# 4_half.net
KiCad netlist of a schematic drawn in Altium Designer
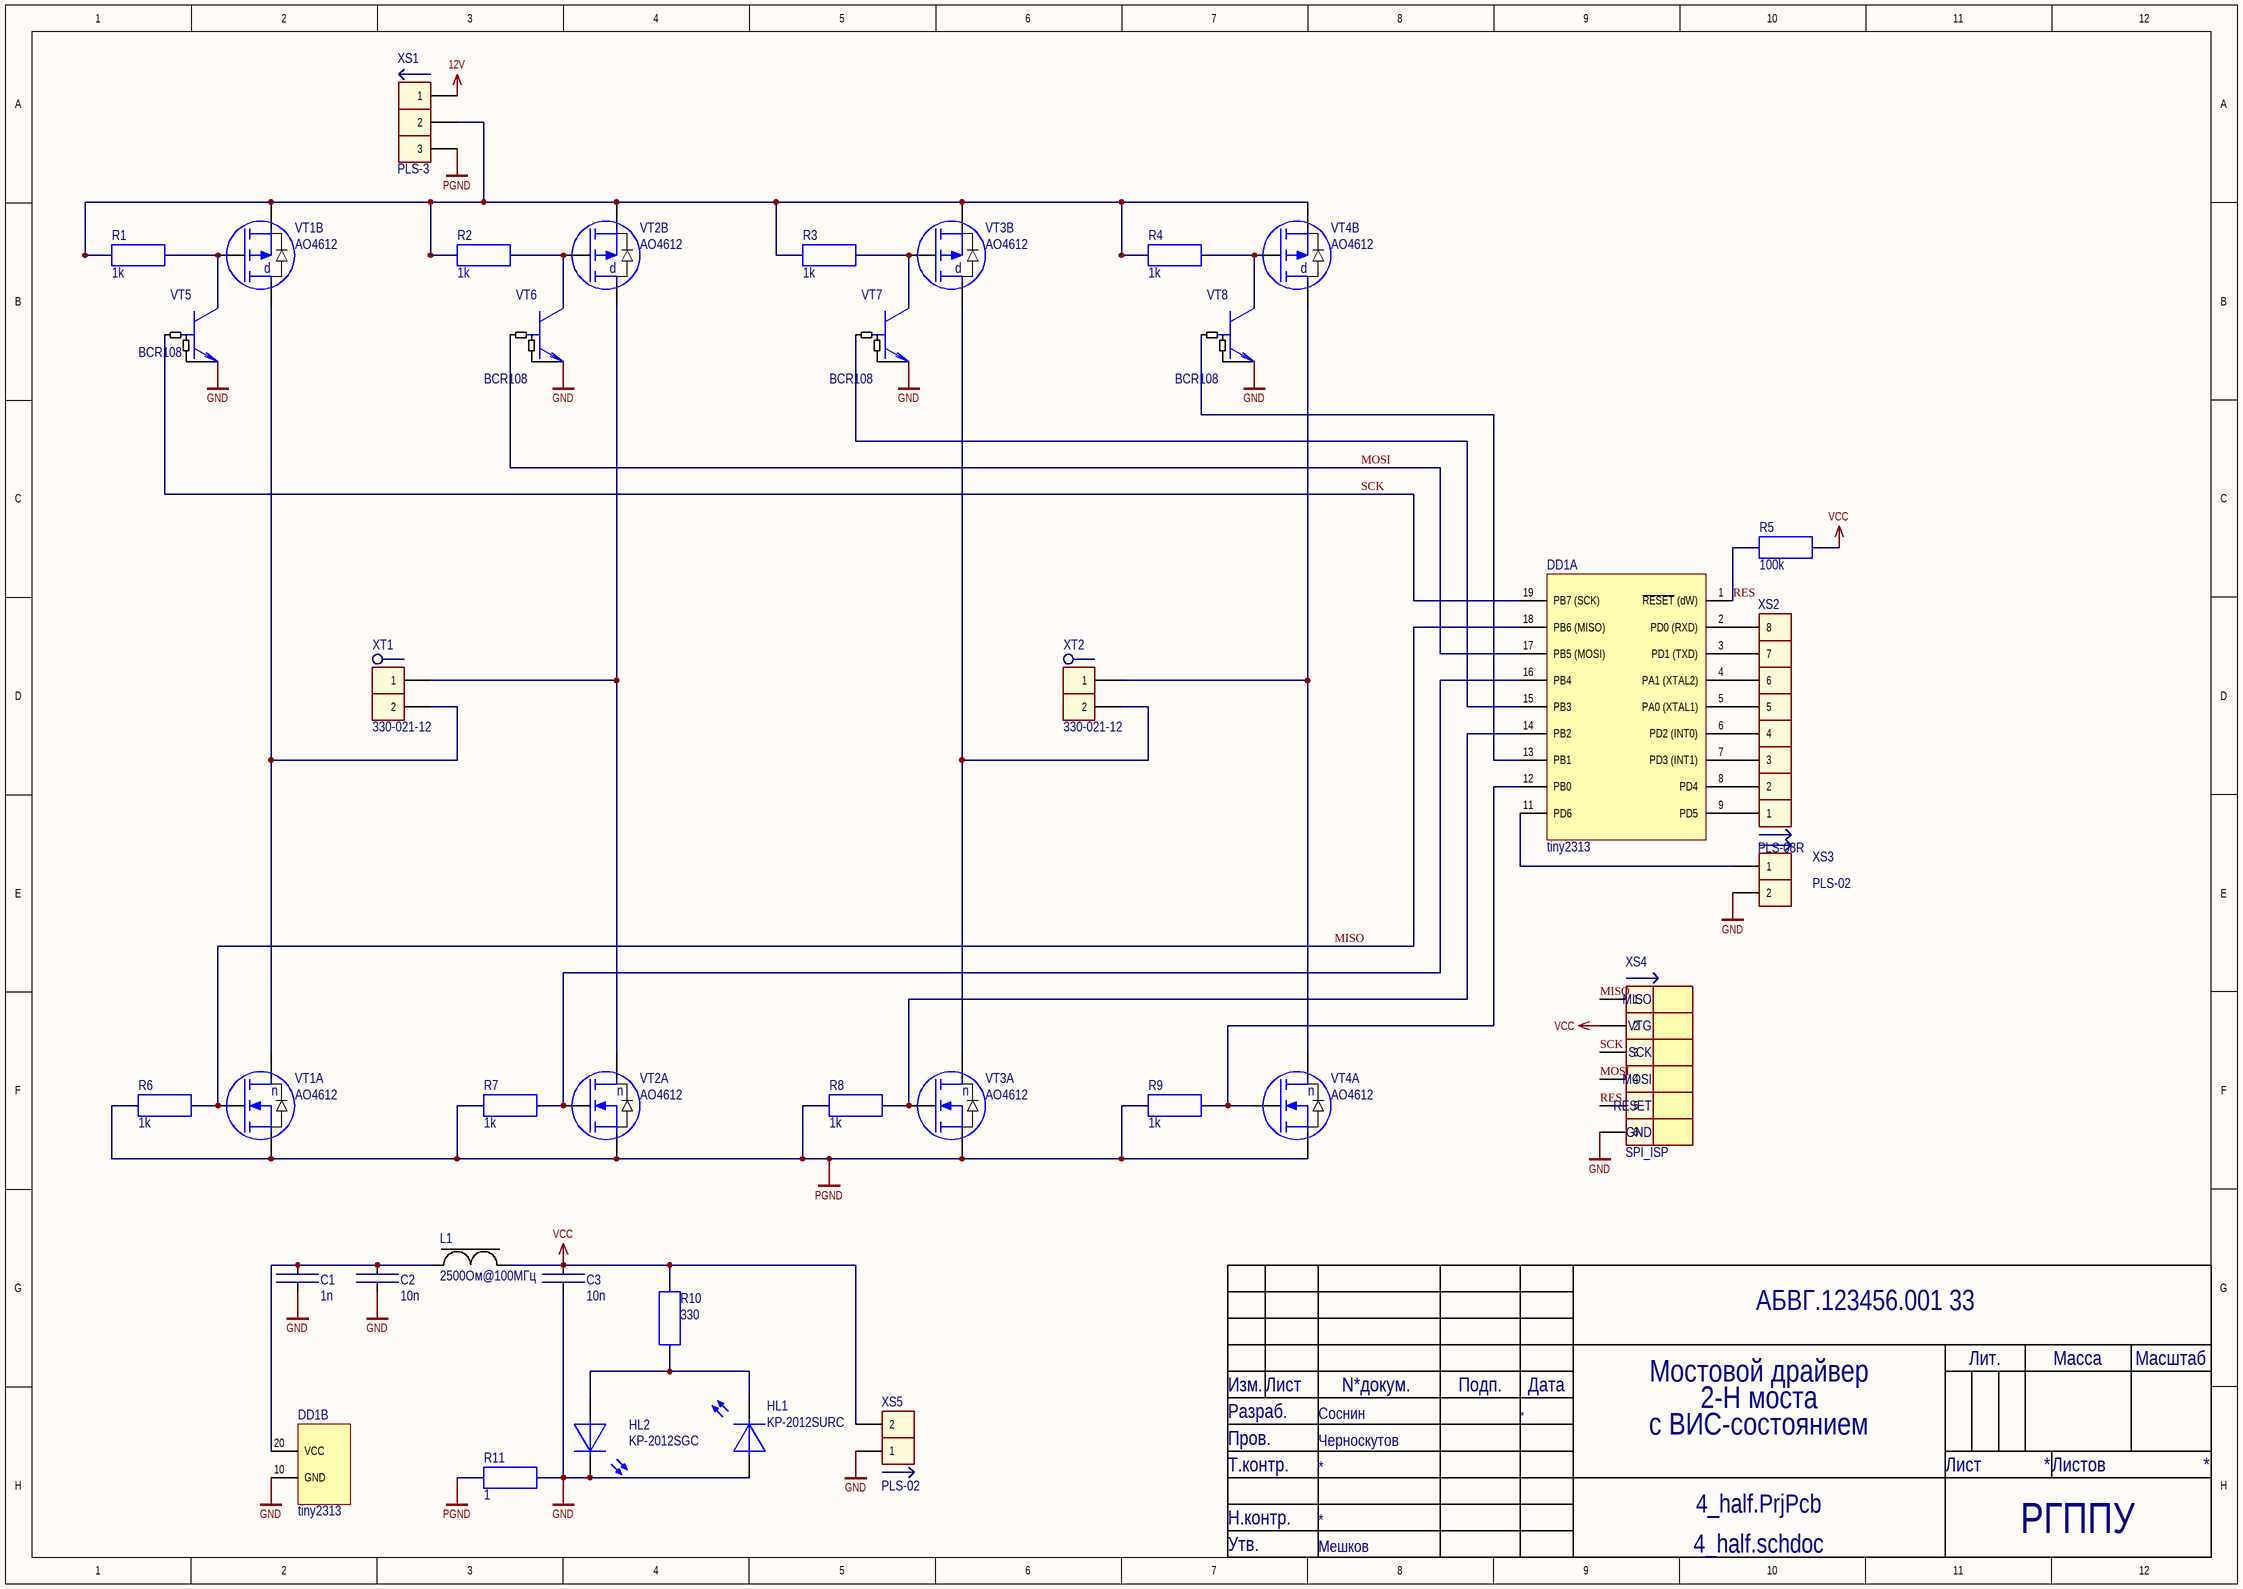
[diagram p0: 4_half.schdoc]

(export (version "E")
  (design (tool "Eeschema 10.0.6"))
  (components
    (comp (ref "C1")
      (value "1n")
      (footprint "SMDRC0805")
      (description "Generic capasitor non-polar")
      (fields (field (name "PARTNUMBER") "Capacitor 0805 1n"))
      (libsource (lib "library") (part "Capacitor"))
    )
    (comp (ref "C2")
      (value "10n")
      (footprint "SMDRC0805")
      (description "Generic capasitor non-polar")
      (fields (field (name "PARTNUMBER") "Capacitor 0805 10n"))
      (libsource (lib "library") (part "Capacitor"))
    )
    (comp (ref "C3")
      (value "10n")
      (footprint "SMDRC0805")
      (description "Generic capasitor non-polar")
      (fields (field (name "PARTNUMBER") "Capacitor 0805 10n"))
      (libsource (lib "library") (part "Capacitor"))
    )
    (comp (ref "DD1")
      (value "tiny2313")
      (footprint "Standard:DIP20")
      (description "Microcontroller 8-bit")
      (fields (field (name "MANUFACTURERPARTNUMBER") "ATTINY2313A-PU") (field (name "MANUFACTURER") "Atmel"))
      (libsource (lib "") (part "ATTINY2313A-PU_1"))
    )
    (comp (ref "HL1")
      (value "KP-2012SURC")
      (footprint "Indicator:DIOMELF2012M")
      (description "Diod LED SMD Red")
      (libsource (lib "Indicator") (part "LED1_R"))
    )
    (comp (ref "HL2")
      (value "KP-2012SGC")
      (footprint "Indicator:DIOMELF2012M")
      (description "Diod LED SMD Green")
      (libsource (lib "Indicator") (part "LED1_G"))
    )
    (comp (ref "L1")
      (value "2500Ом@100МГц")
      (footprint "Inductor:MMZ1608")
      (description "Феррит 2500Ом@100МГц")
      (fields (field (name "MANUFACTURERPARTNUMBER") "MMZ1608A252B") (field (name "MANUFACTURER") "TDK"))
      (libsource (lib "Inductor") (part "MMZ1608A252B"))
    )
    (comp (ref "R1")
      (value "1k")
      (footprint "SMDRC0805")
      (description "Generic resistor")
      (fields (field (name "PARTNUMBER") "Resistor 0805 1k"))
      (libsource (lib "library") (part "Resistor"))
    )
    (comp (ref "R2")
      (value "1k")
      (footprint "SMDRC0805")
      (description "Generic resistor")
      (fields (field (name "PARTNUMBER") "Resistor 0805 1k"))
      (libsource (lib "library") (part "Resistor"))
    )
    (comp (ref "R3")
      (value "1k")
      (footprint "SMDRC0805")
      (description "Generic resistor")
      (fields (field (name "PARTNUMBER") "Resistor 0805 1k"))
      (libsource (lib "library") (part "Resistor"))
    )
    (comp (ref "R4")
      (value "1k")
      (footprint "SMDRC0805")
      (description "Generic resistor")
      (fields (field (name "PARTNUMBER") "Resistor 0805 1k"))
      (libsource (lib "library") (part "Resistor"))
    )
    (comp (ref "R5")
      (value "100k")
      (footprint "SMDRC0805")
      (description "Generic resistor")
      (fields (field (name "PARTNUMBER") "Resistor 0805 100k"))
      (libsource (lib "library") (part "Resistor"))
    )
    (comp (ref "R6")
      (value "1k")
      (footprint "SMDRC0805")
      (description "Generic resistor")
      (fields (field (name "PARTNUMBER") "Resistor 0805 1k"))
      (libsource (lib "library") (part "Resistor"))
    )
    (comp (ref "R7")
      (value "1k")
      (footprint "SMDRC0805")
      (description "Generic resistor")
      (fields (field (name "PARTNUMBER") "Resistor 0805 1k"))
      (libsource (lib "library") (part "Resistor"))
    )
    (comp (ref "R8")
      (value "1k")
      (footprint "SMDRC0805")
      (description "Generic resistor")
      (fields (field (name "PARTNUMBER") "Resistor 0805 1k"))
      (libsource (lib "library") (part "Resistor"))
    )
    (comp (ref "R9")
      (value "1k")
      (footprint "SMDRC0805")
      (description "Generic resistor")
      (fields (field (name "PARTNUMBER") "Resistor 0805 1k"))
      (libsource (lib "library") (part "Resistor"))
    )
    (comp (ref "R10")
      (value "330")
      (footprint "SMDRC0805")
      (description "Generic resistor")
      (fields (field (name "PARTNUMBER") "Resistor 0805 330"))
      (libsource (lib "") (part "Resistor_1"))
    )
    (comp (ref "R11")
      (value "1")
      (footprint "SMDRC0805")
      (description "Generic resistor")
      (fields (field (name "PARTNUMBER") "Resistor 0805 1"))
      (libsource (lib "library") (part "Resistor"))
    )
    (comp (ref "VT1")
      (value "AO4612")
      (footprint "Standard:SOIC-8-Narrow")
      (description "p-n пара комплиментарная 60В")
      (fields (field (name "MANUFACTURER") "AO (Alpha & Omega semiconductor)"))
      (libsource (lib "Transistor") (part "AO4612"))
    )
    (comp (ref "VT2")
      (value "AO4612")
      (footprint "Standard:SOIC-8-Narrow")
      (description "p-n пара комплиментарная 60В")
      (fields (field (name "MANUFACTURER") "AO (Alpha & Omega semiconductor)"))
      (libsource (lib "Transistor") (part "AO4612"))
    )
    (comp (ref "VT3")
      (value "AO4612")
      (footprint "Standard:SOIC-8-Narrow")
      (description "p-n пара комплиментарная 60В")
      (fields (field (name "MANUFACTURER") "AO (Alpha & Omega semiconductor)"))
      (libsource (lib "Transistor") (part "AO4612"))
    )
    (comp (ref "VT4")
      (value "AO4612")
      (footprint "Standard:SOIC-8-Narrow")
      (description "p-n пара комплиментарная 60В")
      (fields (field (name "MANUFACTURER") "AO (Alpha & Omega semiconductor)"))
      (libsource (lib "Transistor") (part "AO4612"))
    )
    (comp (ref "VT5")
      (value "BCR108")
      (footprint "Transistor:SOT95P245X110-3M")
      (description "n-p-n цифровой")
      (fields
        (field (name "MANUFACTURER") "Infineon Technologies")
        (field (name "MANUFACTURERPARTNUMBER") "BCR108E6327")
      )
      (libsource (lib "Transistor") (part "BCR108E6327"))
    )
    (comp (ref "VT6")
      (value "BCR108")
      (footprint "Transistor:SOT95P245X110-3M")
      (description "n-p-n цифровой")
      (fields
        (field (name "MANUFACTURER") "Infineon Technologies")
        (field (name "MANUFACTURERPARTNUMBER") "BCR108E6327")
      )
      (libsource (lib "Transistor") (part "BCR108E6327"))
    )
    (comp (ref "VT7")
      (value "BCR108")
      (footprint "Transistor:SOT95P245X110-3M")
      (description "n-p-n цифровой")
      (fields
        (field (name "MANUFACTURER") "Infineon Technologies")
        (field (name "MANUFACTURERPARTNUMBER") "BCR108E6327")
      )
      (libsource (lib "Transistor") (part "BCR108E6327"))
    )
    (comp (ref "VT8")
      (value "BCR108")
      (footprint "Transistor:SOT95P245X110-3M")
      (description "n-p-n цифровой")
      (fields
        (field (name "MANUFACTURER") "Infineon Technologies")
        (field (name "MANUFACTURERPARTNUMBER") "BCR108E6327")
      )
      (libsource (lib "Transistor") (part "BCR108E6327"))
    )
    (comp (ref "XS1")
      (value "partnumber")
      (footprint "Connector:PLS-03")
      (description "Male 3-pin connection")
      (fields (field (name "MANUFACTURERPARTNUMBER") "PLS-3"))
      (libsource (lib "Connector") (part "Con3_M_PLS-3"))
    )
    (comp (ref "XS2")
      (value "partnumber")
      (footprint "Connector:PLS-08R1")
      (description "Male 8-pin connection")
      (fields (field (name "MANUFACTURERPARTNUMBER") "PLS-08R"))
      (libsource (lib "Connector") (part "Con8_M PLS-08MR"))
    )
    (comp (ref "XS3")
      (value "PLS-02")
      (footprint "Connector:PLS-02")
      (description "Male 2-pin connection")
      (fields (field (name "MANUFACTURER") "AUK"))
      (libsource (lib "") (part "Con2_M_PLS-02_1"))
    )
    (comp (ref "XS4")
      (value "SPI_ISP")
      (footprint "Connector:IDC-06M")
      (description "SPI connector")
      (fields (field (name "MANUFACTURERPARTNUMBER") "IDC-06M"))
      (libsource (lib "Connector") (part "Con6_M IDC-06M_SPI"))
    )
    (comp (ref "XS5")
      (value "PLS-02")
      (footprint "Connector:PLS-02")
      (description "Male 2-pin connection")
      (fields (field (name "MANUFACTURER") "AUK"))
      (libsource (lib "Connector") (part "Con2_M_PLS-02"))
    )
    (comp (ref "XT1")
      (value "330-021-12")
      (footprint "330-021-12")
      (description "Demountable connection  2-pin")
      (fields (field (name "MANUFACTURER") "Degson Electronics Co., Ltd"))
      (libsource (lib "Connector") (part "Con2_D 330-021-12"))
    )
    (comp (ref "XT2")
      (value "330-021-12")
      (footprint "330-021-12")
      (description "Demountable connection  2-pin")
      (fields (field (name "MANUFACTURER") "Degson Electronics Co., Ltd"))
      (libsource (lib "Connector") (part "Con2_D 330-021-12"))
    )
  )
  (nets
    (net (code "1") (name "/MISO") (class "Default")
      (node (ref "DD1") (pin "18") (pinfunction "PB6_(MISO)_18") (pintype "passive"))
      (node (ref "R6") (pin "2") (pinfunction "2_2") (pintype "passive"))
      (node (ref "VT1") (pin "2") (pinfunction "G2_2") (pintype "passive"))
      (node (ref "XS4") (pin "1") (pinfunction "1_1") (pintype "passive"))
    )
    (net (code "2") (name "/MOSI") (class "Default")
      (node (ref "DD1") (pin "17") (pinfunction "PB5_(MOSI)_17") (pintype "passive"))
      (node (ref "VT6") (pin "1") (pinfunction "B_1") (pintype "passive"))
      (node (ref "XS4") (pin "4") (pinfunction "4_4") (pintype "passive"))
    )
    (net (code "3") (name "/RES") (class "Default")
      (node (ref "DD1") (pin "1") (pinfunction "~{RESET}_(dW)_1") (pintype "passive"))
      (node (ref "R5") (pin "1") (pinfunction "1_1") (pintype "passive"))
      (node (ref "XS4") (pin "5") (pinfunction "5_5") (pintype "passive"))
    )
    (net (code "4") (name "/SCK") (class "Default")
      (node (ref "DD1") (pin "19") (pinfunction "PB7_(SCK)_19") (pintype "passive"))
      (node (ref "VT5") (pin "1") (pinfunction "B_1") (pintype "passive"))
      (node (ref "XS4") (pin "3") (pinfunction "3_3") (pintype "passive"))
    )
    (net (code "5") (name "12V") (class "Default")
      (node (ref "XS1") (pin "1") (pinfunction "1_1") (pintype "passive"))
    )
    (net (code "6") (name "GND") (class "Default")
      (node (ref "C1") (pin "1") (pintype "passive"))
      (node (ref "C2") (pin "1") (pintype "passive"))
      (node (ref "C3") (pin "1") (pintype "passive"))
      (node (ref "DD1") (pin "10") (pinfunction "GND_10") (pintype "passive"))
      (node (ref "HL1") (pin "1") (pinfunction "1_1") (pintype "passive"))
      (node (ref "HL2") (pin "2") (pinfunction "2_2") (pintype "passive"))
      (node (ref "R11") (pin "2") (pinfunction "2_2") (pintype "passive"))
      (node (ref "VT5") (pin "2") (pinfunction "E_2") (pintype "passive"))
      (node (ref "VT6") (pin "2") (pinfunction "E_2") (pintype "passive"))
      (node (ref "VT7") (pin "2") (pinfunction "E_2") (pintype "passive"))
      (node (ref "VT8") (pin "2") (pinfunction "E_2") (pintype "passive"))
      (node (ref "XS3") (pin "2") (pinfunction "2_2") (pintype "passive"))
      (node (ref "XS4") (pin "6") (pinfunction "6_6") (pintype "passive"))
      (node (ref "XS5") (pin "1") (pinfunction "1_1") (pintype "passive"))
    )
    (net (code "7") (name "Net-(DD1A-PA0_(XTAL1))") (class "Default")
      (node (ref "DD1") (pin "5") (pinfunction "PA0_(XTAL1)_5") (pintype "passive"))
      (node (ref "XS2") (pin "5") (pinfunction "5_5") (pintype "passive"))
    )
    (net (code "8") (name "Net-(DD1A-PA1_(XTAL2))") (class "Default")
      (node (ref "DD1") (pin "4") (pinfunction "PA1_(XTAL2)_4") (pintype "passive"))
      (node (ref "XS2") (pin "6") (pinfunction "6_6") (pintype "passive"))
    )
    (net (code "9") (name "Net-(DD1A-PB0)") (class "Default")
      (node (ref "DD1") (pin "12") (pinfunction "PB0_12") (pintype "passive"))
      (node (ref "R9") (pin "2") (pinfunction "2_2") (pintype "passive"))
      (node (ref "VT4") (pin "2") (pinfunction "G2_2") (pintype "passive"))
    )
    (net (code "10") (name "Net-(DD1A-PB1)") (class "Default")
      (node (ref "DD1") (pin "13") (pinfunction "PB1_13") (pintype "passive"))
      (node (ref "VT8") (pin "1") (pinfunction "B_1") (pintype "passive"))
    )
    (net (code "11") (name "Net-(DD1A-PB2)") (class "Default")
      (node (ref "DD1") (pin "14") (pinfunction "PB2_14") (pintype "passive"))
      (node (ref "R8") (pin "2") (pinfunction "2_2") (pintype "passive"))
      (node (ref "VT3") (pin "2") (pinfunction "G2_2") (pintype "passive"))
    )
    (net (code "12") (name "Net-(DD1A-PB3)") (class "Default")
      (node (ref "DD1") (pin "15") (pinfunction "PB3_15") (pintype "passive"))
      (node (ref "VT7") (pin "1") (pinfunction "B_1") (pintype "passive"))
    )
    (net (code "13") (name "Net-(DD1A-PB4)") (class "Default")
      (node (ref "DD1") (pin "16") (pinfunction "PB4_16") (pintype "passive"))
      (node (ref "R7") (pin "2") (pinfunction "2_2") (pintype "passive"))
      (node (ref "VT2") (pin "2") (pinfunction "G2_2") (pintype "passive"))
    )
    (net (code "14") (name "Net-(DD1A-PD0_(RXD))") (class "Default")
      (node (ref "DD1") (pin "2") (pinfunction "PD0_(RXD)_2") (pintype "passive"))
      (node (ref "XS2") (pin "8") (pinfunction "8_8") (pintype "passive"))
    )
    (net (code "15") (name "Net-(DD1A-PD1_(TXD))") (class "Default")
      (node (ref "DD1") (pin "3") (pinfunction "PD1_(TXD)_3") (pintype "passive"))
      (node (ref "XS2") (pin "7") (pinfunction "7_7") (pintype "passive"))
    )
    (net (code "16") (name "Net-(DD1A-PD2_(INT0))") (class "Default")
      (node (ref "DD1") (pin "6") (pinfunction "PD2_(INT0)_6") (pintype "passive"))
      (node (ref "XS2") (pin "4") (pinfunction "4_4") (pintype "passive"))
    )
    (net (code "17") (name "Net-(DD1A-PD3_(INT1))") (class "Default")
      (node (ref "DD1") (pin "7") (pinfunction "PD3_(INT1)_7") (pintype "passive"))
      (node (ref "XS2") (pin "3") (pinfunction "3_3") (pintype "passive"))
    )
    (net (code "18") (name "Net-(DD1A-PD4)") (class "Default")
      (node (ref "DD1") (pin "8") (pinfunction "PD4_8") (pintype "passive"))
      (node (ref "XS2") (pin "2") (pinfunction "2_2") (pintype "passive"))
    )
    (net (code "19") (name "Net-(DD1A-PD5)") (class "Default")
      (node (ref "DD1") (pin "9") (pinfunction "PD5_9") (pintype "passive"))
      (node (ref "XS2") (pin "1") (pinfunction "1_1") (pintype "passive"))
    )
    (net (code "20") (name "Net-(DD1A-PD6)") (class "Default")
      (node (ref "DD1") (pin "11") (pinfunction "PD6_11") (pintype "passive"))
      (node (ref "XS3") (pin "1") (pinfunction "1_1") (pintype "passive"))
    )
    (net (code "21") (name "Net-(DD1B-VCC)") (class "Default")
      (node (ref "C1") (pin "2") (pintype "passive"))
      (node (ref "C2") (pin "2") (pintype "passive"))
      (node (ref "DD1") (pin "20") (pinfunction "VCC_20") (pintype "passive"))
      (node (ref "L1") (pin "1") (pinfunction "1_1") (pintype "passive"))
    )
    (net (code "22") (name "Net-(HL1-Pad2)") (class "Default")
      (node (ref "HL1") (pin "2") (pinfunction "2_2") (pintype "passive"))
      (node (ref "HL2") (pin "1") (pinfunction "1_1") (pintype "passive"))
      (node (ref "R10") (pin "1") (pinfunction "1_1") (pintype "passive"))
    )
    (net (code "23") (name "Net-(VT1A-D2)") (class "Default")
      (node (ref "VT1") (pin "5") (pinfunction "D1_5") (pintype "passive"))
      (node (ref "VT1") (pin "8") (pinfunction "D2_8") (pintype "passive"))
      (node (ref "XT1") (pin "2") (pinfunction "2_2") (pintype "passive"))
    )
    (net (code "24") (name "Net-(VT1B-G1)") (class "Default")
      (node (ref "R1") (pin "2") (pinfunction "2_2") (pintype "passive"))
      (node (ref "VT1") (pin "4") (pinfunction "G1_4") (pintype "passive"))
      (node (ref "VT5") (pin "3") (pinfunction "C_3") (pintype "passive"))
    )
    (net (code "25") (name "Net-(VT1B-S1)") (class "Default")
      (node (ref "R1") (pin "1") (pinfunction "1_1") (pintype "passive"))
      (node (ref "R2") (pin "1") (pinfunction "1_1") (pintype "passive"))
      (node (ref "R3") (pin "1") (pinfunction "1_1") (pintype "passive"))
      (node (ref "R4") (pin "1") (pinfunction "1_1") (pintype "passive"))
      (node (ref "VT1") (pin "3") (pinfunction "S1_3") (pintype "passive"))
      (node (ref "VT2") (pin "3") (pinfunction "S1_3") (pintype "passive"))
      (node (ref "VT3") (pin "3") (pinfunction "S1_3") (pintype "passive"))
      (node (ref "VT4") (pin "3") (pinfunction "S1_3") (pintype "passive"))
      (node (ref "XS1") (pin "2") (pinfunction "2_2") (pintype "passive"))
    )
    (net (code "26") (name "Net-(VT2A-D2)") (class "Default")
      (node (ref "VT2") (pin "5") (pinfunction "D1_5") (pintype "passive"))
      (node (ref "VT2") (pin "8") (pinfunction "D2_8") (pintype "passive"))
      (node (ref "XT1") (pin "1") (pinfunction "1_1") (pintype "passive"))
    )
    (net (code "27") (name "Net-(VT2B-G1)") (class "Default")
      (node (ref "R2") (pin "2") (pinfunction "2_2") (pintype "passive"))
      (node (ref "VT2") (pin "4") (pinfunction "G1_4") (pintype "passive"))
      (node (ref "VT6") (pin "3") (pinfunction "C_3") (pintype "passive"))
    )
    (net (code "28") (name "Net-(VT3A-D2)") (class "Default")
      (node (ref "VT3") (pin "5") (pinfunction "D1_5") (pintype "passive"))
      (node (ref "VT3") (pin "8") (pinfunction "D2_8") (pintype "passive"))
      (node (ref "XT2") (pin "2") (pinfunction "2_2") (pintype "passive"))
    )
    (net (code "29") (name "Net-(VT3B-G1)") (class "Default")
      (node (ref "R3") (pin "2") (pinfunction "2_2") (pintype "passive"))
      (node (ref "VT3") (pin "4") (pinfunction "G1_4") (pintype "passive"))
      (node (ref "VT7") (pin "3") (pinfunction "C_3") (pintype "passive"))
    )
    (net (code "30") (name "Net-(VT4A-D2)") (class "Default")
      (node (ref "VT4") (pin "5") (pinfunction "D1_5") (pintype "passive"))
      (node (ref "VT4") (pin "8") (pinfunction "D2_8") (pintype "passive"))
      (node (ref "XT2") (pin "1") (pinfunction "1_1") (pintype "passive"))
    )
    (net (code "31") (name "Net-(VT4B-G1)") (class "Default")
      (node (ref "R4") (pin "2") (pinfunction "2_2") (pintype "passive"))
      (node (ref "VT4") (pin "4") (pinfunction "G1_4") (pintype "passive"))
      (node (ref "VT8") (pin "3") (pinfunction "C_3") (pintype "passive"))
    )
    (net (code "32") (name "PGND") (class "Default")
      (node (ref "R11") (pin "1") (pinfunction "1_1") (pintype "passive"))
      (node (ref "R6") (pin "1") (pinfunction "1_1") (pintype "passive"))
      (node (ref "R7") (pin "1") (pinfunction "1_1") (pintype "passive"))
      (node (ref "R8") (pin "1") (pinfunction "1_1") (pintype "passive"))
      (node (ref "R9") (pin "1") (pinfunction "1_1") (pintype "passive"))
      (node (ref "VT1") (pin "1") (pinfunction "S2_1") (pintype "passive"))
      (node (ref "VT2") (pin "1") (pinfunction "S2_1") (pintype "passive"))
      (node (ref "VT3") (pin "1") (pinfunction "S2_1") (pintype "passive"))
      (node (ref "VT4") (pin "1") (pinfunction "S2_1") (pintype "passive"))
      (node (ref "XS1") (pin "3") (pinfunction "3_3") (pintype "passive"))
    )
    (net (code "33") (name "VCC") (class "Default")
      (node (ref "C3") (pin "2") (pintype "passive"))
      (node (ref "L1") (pin "2") (pinfunction "2_2") (pintype "passive"))
      (node (ref "R10") (pin "2") (pinfunction "2_2") (pintype "passive"))
      (node (ref "R5") (pin "2") (pinfunction "2_2") (pintype "passive"))
      (node (ref "XS4") (pin "2") (pinfunction "2_2") (pintype "passive"))
      (node (ref "XS5") (pin "2") (pinfunction "2_2") (pintype "passive"))
    )
  )
)
